# HDMI_CONVERTER.net
KiCad netlist of a schematic drawn in Altium Designer
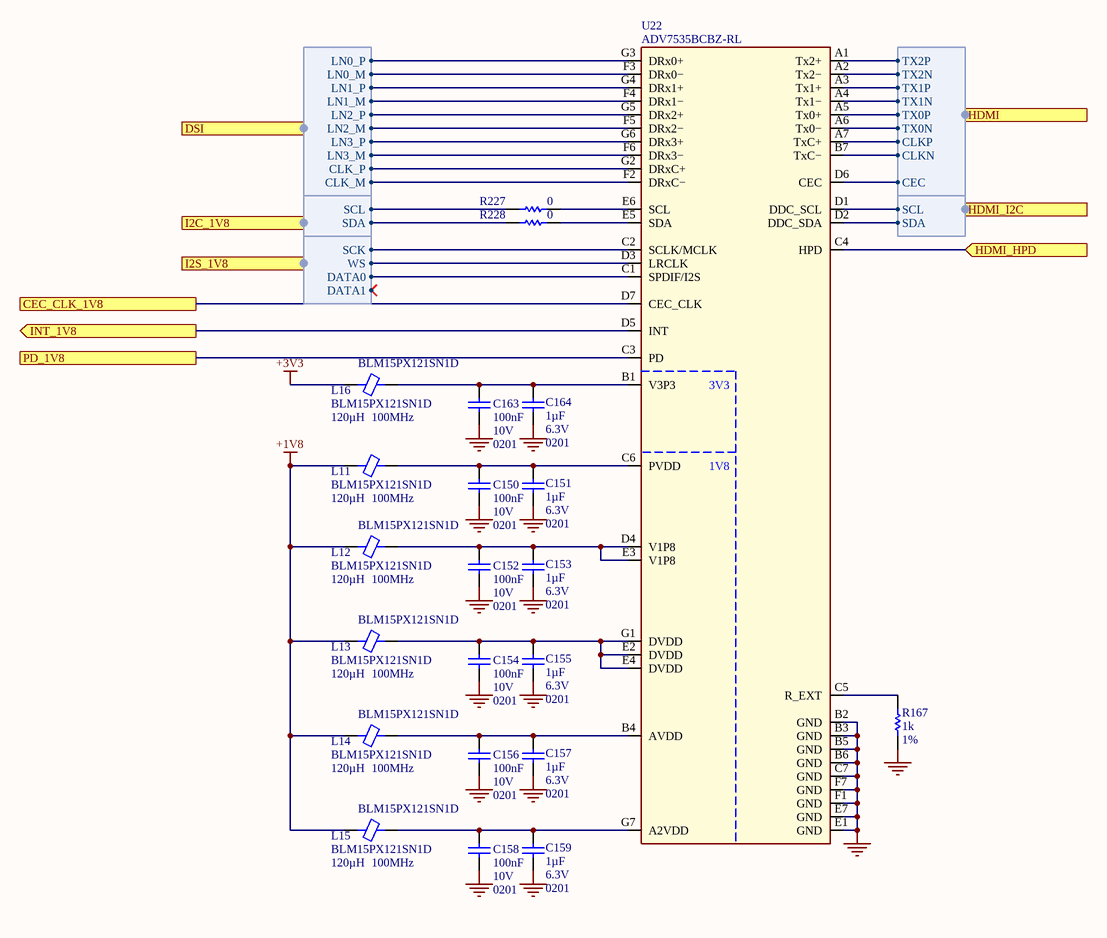
[diagram p0: HDMI_CONVERTER.SchDoc]

(export (version "E")
  (design (tool "Eeschema 10.0.6"))
  (components
    (comp (ref "C150")
      (value "100nF")
      (footprint "CAP-0201")
      (description "CAP CHIP 0201 100nF 10% 10V X5R")
      (fields
        (field (name "PART NUMBER") "CL03A104KP3NNNC")
        (field (name "MANUFACTURER") "Samsung Electro-Mechanics")
        (field (name "VOLTAGE") "10V")
        (field (name "CASE CODE (IMPERIAL)") "0201")
      )
      (libsource (lib "Clean") (part "CAP"))
    )
    (comp (ref "C151")
      (value "1µF")
      (footprint "CAP-0201")
      (description "CAP CHIP 0201 1uF 20% 6.3V X5R")
      (fields
        (field (name "VOLTAGE") "6.3V")
        (field (name "TOLERANCE") "20%")
        (field (name "PART NUMBER") "GRM033R60J105MEA2D")
        (field (name "CASE CODE (IMPERIAL)") "0201")
      )
      (libsource (lib "Clean") (part "CAP"))
    )
    (comp (ref "C152")
      (value "100nF")
      (footprint "CAP-0201")
      (description "CAP CHIP 0201 100nF 10% 10V X5R")
      (fields
        (field (name "PART NUMBER") "CL03A104KP3NNNC")
        (field (name "MANUFACTURER") "Samsung Electro-Mechanics")
        (field (name "VOLTAGE") "10V")
        (field (name "CASE CODE (IMPERIAL)") "0201")
      )
      (libsource (lib "Clean") (part "CAP"))
    )
    (comp (ref "C153")
      (value "1µF")
      (footprint "CAP-0201")
      (description "CAP CHIP 0201 1uF 20% 6.3V X5R")
      (fields
        (field (name "VOLTAGE") "6.3V")
        (field (name "TOLERANCE") "20%")
        (field (name "PART NUMBER") "GRM033R60J105MEA2D")
        (field (name "CASE CODE (IMPERIAL)") "0201")
      )
      (libsource (lib "Clean") (part "CAP"))
    )
    (comp (ref "C154")
      (value "100nF")
      (footprint "CAP-0201")
      (description "CAP CHIP 0201 100nF 10% 10V X5R")
      (fields
        (field (name "PART NUMBER") "CL03A104KP3NNNC")
        (field (name "MANUFACTURER") "Samsung Electro-Mechanics")
        (field (name "VOLTAGE") "10V")
        (field (name "CASE CODE (IMPERIAL)") "0201")
      )
      (libsource (lib "Clean") (part "CAP"))
    )
    (comp (ref "C155")
      (value "1µF")
      (footprint "CAP-0201")
      (description "CAP CHIP 0201 1uF 20% 6.3V X5R")
      (fields
        (field (name "VOLTAGE") "6.3V")
        (field (name "TOLERANCE") "20%")
        (field (name "PART NUMBER") "GRM033R60J105MEA2D")
        (field (name "CASE CODE (IMPERIAL)") "0201")
      )
      (libsource (lib "Clean") (part "CAP"))
    )
    (comp (ref "C156")
      (value "100nF")
      (footprint "CAP-0201")
      (description "CAP CHIP 0201 100nF 10% 10V X5R")
      (fields
        (field (name "PART NUMBER") "CL03A104KP3NNNC")
        (field (name "MANUFACTURER") "Samsung Electro-Mechanics")
        (field (name "VOLTAGE") "10V")
        (field (name "CASE CODE (IMPERIAL)") "0201")
      )
      (libsource (lib "Clean") (part "CAP"))
    )
    (comp (ref "C157")
      (value "1µF")
      (footprint "CAP-0201")
      (description "CAP CHIP 0201 1uF 20% 6.3V X5R")
      (fields
        (field (name "VOLTAGE") "6.3V")
        (field (name "TOLERANCE") "20%")
        (field (name "PART NUMBER") "GRM033R60J105MEA2D")
        (field (name "CASE CODE (IMPERIAL)") "0201")
      )
      (libsource (lib "Clean") (part "CAP"))
    )
    (comp (ref "C158")
      (value "100nF")
      (footprint "CAP-0201")
      (description "CAP CHIP 0201 100nF 10% 10V X5R")
      (fields
        (field (name "PART NUMBER") "CL03A104KP3NNNC")
        (field (name "MANUFACTURER") "Samsung Electro-Mechanics")
        (field (name "VOLTAGE") "10V")
        (field (name "CASE CODE (IMPERIAL)") "0201")
      )
      (libsource (lib "Clean") (part "CAP"))
    )
    (comp (ref "C159")
      (value "1µF")
      (footprint "CAP-0201")
      (description "CAP CHIP 0201 1uF 20% 6.3V X5R")
      (fields
        (field (name "VOLTAGE") "6.3V")
        (field (name "TOLERANCE") "20%")
        (field (name "PART NUMBER") "GRM033R60J105MEA2D")
        (field (name "CASE CODE (IMPERIAL)") "0201")
      )
      (libsource (lib "Clean") (part "CAP"))
    )
    (comp (ref "C163")
      (value "100nF")
      (footprint "CAP-0201")
      (description "CAP CHIP 0201 100nF 10% 10V X5R")
      (fields
        (field (name "PART NUMBER") "CL03A104KP3NNNC")
        (field (name "MANUFACTURER") "Samsung Electro-Mechanics")
        (field (name "VOLTAGE") "10V")
        (field (name "CASE CODE (IMPERIAL)") "0201")
      )
      (libsource (lib "Clean") (part "CAP"))
    )
    (comp (ref "C164")
      (value "1µF")
      (footprint "CAP-0201")
      (description "CAP CHIP 0201 1uF 20% 6.3V X5R")
      (fields
        (field (name "VOLTAGE") "6.3V")
        (field (name "TOLERANCE") "20%")
        (field (name "PART NUMBER") "GRM033R60J105MEA2D")
        (field (name "CASE CODE (IMPERIAL)") "0201")
      )
      (libsource (lib "Clean") (part "CAP"))
    )
    (comp (ref "L11")
      (value "BLM15PX121SN1D")
      (footprint "L-0402")
      (description "FERRITE SMD 0402 120Ohm 25% 100MHz Ferrite 2A")
      (fields
        (field (name "INDUCTANCE") "120µH")
        (field (name "TEST FREQUENCY") "100MHz")
        (field (name "MANUFACTURER") "Murata")
        (field (name "TOLERANCE") "25%")
      )
      (libsource (lib "Clean") (part "Ferrite"))
    )
    (comp (ref "L12")
      (value "BLM15PX121SN1D")
      (footprint "L-0402")
      (description "FERRITE SMD 0402 120Ohm 25% 100MHz Ferrite 2A")
      (fields
        (field (name "INDUCTANCE") "120µH")
        (field (name "TEST FREQUENCY") "100MHz")
        (field (name "MANUFACTURER") "Murata")
        (field (name "TOLERANCE") "25%")
        (field (name "PART NUMBER") "BLM15PX121SN1D")
      )
      (libsource (lib "Clean") (part "Ferrite"))
    )
    (comp (ref "L13")
      (value "BLM15PX121SN1D")
      (footprint "L-0402")
      (description "FERRITE SMD 0402 120Ohm 25% 100MHz Ferrite 2A")
      (fields
        (field (name "INDUCTANCE") "120µH")
        (field (name "TEST FREQUENCY") "100MHz")
        (field (name "MANUFACTURER") "Murata")
        (field (name "TOLERANCE") "25%")
        (field (name "PART NUMBER") "BLM15PX121SN1D")
      )
      (libsource (lib "Clean") (part "Ferrite"))
    )
    (comp (ref "L14")
      (value "BLM15PX121SN1D")
      (footprint "L-0402")
      (description "FERRITE SMD 0402 120Ohm 25% 100MHz Ferrite 2A")
      (fields
        (field (name "INDUCTANCE") "120µH")
        (field (name "TEST FREQUENCY") "100MHz")
        (field (name "MANUFACTURER") "Murata")
        (field (name "TOLERANCE") "25%")
        (field (name "PART NUMBER") "BLM15PX121SN1D")
      )
      (libsource (lib "Clean") (part "Ferrite"))
    )
    (comp (ref "L15")
      (value "BLM15PX121SN1D")
      (footprint "L-0402")
      (description "FERRITE SMD 0402 120Ohm 25% 100MHz Ferrite 2A")
      (fields
        (field (name "INDUCTANCE") "120µH")
        (field (name "TEST FREQUENCY") "100MHz")
        (field (name "MANUFACTURER") "Murata")
        (field (name "TOLERANCE") "25%")
        (field (name "PART NUMBER") "BLM15PX121SN1D")
      )
      (libsource (lib "Clean") (part "Ferrite"))
    )
    (comp (ref "L16")
      (value "BLM15PX121SN1D")
      (footprint "L-0402")
      (description "FERRITE SMD 0402 120Ohm 25% 100MHz Ferrite 2A")
      (fields
        (field (name "INDUCTANCE") "120µH")
        (field (name "TEST FREQUENCY") "100MHz")
        (field (name "MANUFACTURER") "Murata")
        (field (name "TOLERANCE") "25%")
        (field (name "PART NUMBER") "BLM15PX121SN1D")
      )
      (libsource (lib "Clean") (part "Ferrite"))
    )
    (comp (ref "R167")
      (value "1k")
      (footprint "RES-0201")
      (description "RES CHIP 0201 1k 1% 1/20W")
      (fields
        (field (name "PART NUMBER") "RC0201FR-071KL")
        (field (name "TOLERANCE") "1%")
        (field (name "POWER") "50mW")
      )
      (libsource (lib "Clean") (part "RES"))
    )
    (comp (ref "R227")
      (value "0")
      (footprint "RES-0201")
      (description "RES CHIP 0201 0R")
      (fields (field (name "MANUFACTURER") "Vishay") (field (name "PART NUMBER") "CRCW02010000Z0ED"))
      (libsource (lib "Clean") (part "RES"))
    )
    (comp (ref "R228")
      (value "0")
      (footprint "RES-0201")
      (description "RES CHIP 0201 0R")
      (fields (field (name "MANUFACTURER") "Vishay") (field (name "PART NUMBER") "CRCW02010000Z0ED"))
      (libsource (lib "Clean") (part "RES"))
    )
    (comp (ref "U22")
      (value "ADV7535BCBZ-RL")
      (footprint "Analog Devices CB-49-1 WLCSP49 7x7 pitch 0.5mm 3.5x3.5mm")
      (description "IC DSI to HDMI converter, WLCSP49 3.5x3.5mm")
      (fields (field (name "MANUFACTURER") "Analog Devices"))
      (libsource (lib "Clean") (part "ADV7535BCBZ-RL-Symbol-1"))
    )
  )
  (nets
    (net (code "5") (name "+1V8") (class "Default")
      (node (ref "L11") (pin "1") (pinfunction "1_1") (pintype "passive"))
      (node (ref "L12") (pin "1") (pinfunction "1_1") (pintype "passive"))
      (node (ref "L13") (pin "1") (pinfunction "1_1") (pintype "passive"))
      (node (ref "L14") (pin "1") (pinfunction "1_1") (pintype "passive"))
      (node (ref "L15") (pin "1") (pinfunction "1_1") (pintype "passive"))
    )
    (net (code "6") (name "+3V3") (class "Default")
      (node (ref "L16") (pin "1") (pinfunction "1_1") (pintype "passive"))
    )
    (net (code "7") (name "/CEC_CLK_1V8") (class "Default")
      (node (ref "U22") (pin "D7") (pinfunction "CEC_CLK_D7") (pintype "passive"))
    )
    (net (code "8") (name "/HDMI_HPD") (class "Default")
      (node (ref "U22") (pin "C4") (pinfunction "HPD_C4") (pintype "passive"))
    )
    (net (code "10") (name "/INT_1V8") (class "Default")
      (node (ref "U22") (pin "D5") (pinfunction "INT_D5") (pintype "passive"))
    )
    (net (code "11") (name "/PD_1V8") (class "Default")
      (node (ref "U22") (pin "C3") (pinfunction "PD_C3") (pintype "passive"))
    )
    (net (code "15") (name "GND") (class "Default")
      (node (ref "C150") (pin "1") (pinfunction "1_1") (pintype "passive"))
      (node (ref "C151") (pin "1") (pinfunction "1_1") (pintype "passive"))
      (node (ref "C152") (pin "1") (pinfunction "1_1") (pintype "passive"))
      (node (ref "C153") (pin "1") (pinfunction "1_1") (pintype "passive"))
      (node (ref "C154") (pin "1") (pinfunction "1_1") (pintype "passive"))
      (node (ref "C155") (pin "1") (pinfunction "1_1") (pintype "passive"))
      (node (ref "C156") (pin "1") (pinfunction "1_1") (pintype "passive"))
      (node (ref "C157") (pin "1") (pinfunction "1_1") (pintype "passive"))
      (node (ref "C158") (pin "1") (pinfunction "1_1") (pintype "passive"))
      (node (ref "C159") (pin "1") (pinfunction "1_1") (pintype "passive"))
      (node (ref "C163") (pin "1") (pinfunction "1_1") (pintype "passive"))
      (node (ref "C164") (pin "1") (pinfunction "1_1") (pintype "passive"))
      (node (ref "R167") (pin "1") (pinfunction "1_1") (pintype "passive"))
      (node (ref "U22") (pin "B2") (pinfunction "GND_B2") (pintype "passive"))
      (node (ref "U22") (pin "B3") (pinfunction "GND_B3") (pintype "passive"))
      (node (ref "U22") (pin "B5") (pinfunction "GND_B5") (pintype "passive"))
      (node (ref "U22") (pin "B6") (pinfunction "GND_B6") (pintype "passive"))
      (node (ref "U22") (pin "C7") (pinfunction "GND_C7") (pintype "passive"))
      (node (ref "U22") (pin "E1") (pinfunction "GND_E1") (pintype "passive"))
      (node (ref "U22") (pin "E7") (pinfunction "GND_E7") (pintype "passive"))
      (node (ref "U22") (pin "F1") (pinfunction "GND_F1") (pintype "passive"))
      (node (ref "U22") (pin "F7") (pinfunction "GND_F7") (pintype "passive"))
    )
    (net (code "16") (name "Net-(C152-Pad2)") (class "Default")
      (node (ref "C152") (pin "2") (pinfunction "2_2") (pintype "passive"))
      (node (ref "C153") (pin "2") (pinfunction "2_2") (pintype "passive"))
      (node (ref "L12") (pin "2") (pinfunction "2_2") (pintype "passive"))
      (node (ref "U22") (pin "D4") (pinfunction "V1P8_D4") (pintype "passive"))
      (node (ref "U22") (pin "E3") (pinfunction "V1P8_E3") (pintype "passive"))
    )
    (net (code "17") (name "Net-(C154-Pad2)") (class "Default")
      (node (ref "C154") (pin "2") (pinfunction "2_2") (pintype "passive"))
      (node (ref "C155") (pin "2") (pinfunction "2_2") (pintype "passive"))
      (node (ref "L13") (pin "2") (pinfunction "2_2") (pintype "passive"))
      (node (ref "U22") (pin "E2") (pinfunction "DVDD_E2") (pintype "passive"))
      (node (ref "U22") (pin "E4") (pinfunction "DVDD_E4") (pintype "passive"))
      (node (ref "U22") (pin "G1") (pinfunction "DVDD_G1") (pintype "passive"))
    )
    (net (code "18") (name "Net-(U22-A2VDD)") (class "Default")
      (node (ref "C158") (pin "2") (pinfunction "2_2") (pintype "passive"))
      (node (ref "C159") (pin "2") (pinfunction "2_2") (pintype "passive"))
      (node (ref "L15") (pin "2") (pinfunction "2_2") (pintype "passive"))
      (node (ref "U22") (pin "G7") (pinfunction "A2VDD_G7") (pintype "passive"))
    )
    (net (code "19") (name "Net-(U22-AVDD)") (class "Default")
      (node (ref "C156") (pin "2") (pinfunction "2_2") (pintype "passive"))
      (node (ref "C157") (pin "2") (pinfunction "2_2") (pintype "passive"))
      (node (ref "L14") (pin "2") (pinfunction "2_2") (pintype "passive"))
      (node (ref "U22") (pin "B4") (pinfunction "AVDD_B4") (pintype "passive"))
    )
    (net (code "20") (name "Net-(U22-PVDD)") (class "Default")
      (node (ref "C150") (pin "2") (pinfunction "2_2") (pintype "passive"))
      (node (ref "C151") (pin "2") (pinfunction "2_2") (pintype "passive"))
      (node (ref "L11") (pin "2") (pinfunction "2_2") (pintype "passive"))
      (node (ref "U22") (pin "C6") (pinfunction "PVDD_C6") (pintype "passive"))
    )
    (net (code "21") (name "Net-(U22-R_EXT)") (class "Default")
      (node (ref "R167") (pin "2") (pinfunction "2_2") (pintype "passive"))
      (node (ref "U22") (pin "C5") (pinfunction "R_EXT_C5") (pintype "passive"))
    )
    (net (code "22") (name "Net-(U22-SCL)") (class "Default")
      (node (ref "R227") (pin "1") (pinfunction "1_1") (pintype "passive"))
      (node (ref "U22") (pin "E6") (pinfunction "SCL_E6") (pintype "passive"))
    )
    (net (code "23") (name "Net-(U22-SDA)") (class "Default")
      (node (ref "R228") (pin "1") (pinfunction "1_1") (pintype "passive"))
      (node (ref "U22") (pin "E5") (pinfunction "SDA_E5") (pintype "passive"))
    )
    (net (code "24") (name "Net-(U22-V3P3)") (class "Default")
      (node (ref "C163") (pin "2") (pinfunction "2_2") (pintype "passive"))
      (node (ref "C164") (pin "2") (pinfunction "2_2") (pintype "passive"))
      (node (ref "L16") (pin "2") (pinfunction "2_2") (pintype "passive"))
      (node (ref "U22") (pin "B1") (pinfunction "V3P3_B1") (pintype "passive"))
    )
    (net (code "25") (name "unconnected-(R227-Pad2)") (class "Default")
      (node (ref "R227") (pin "2") (pinfunction "2_2") (pintype "passive"))
    )
    (net (code "26") (name "unconnected-(R228-Pad2)") (class "Default")
      (node (ref "R228") (pin "2") (pinfunction "2_2") (pintype "passive"))
    )
    (net (code "27") (name "unconnected-(U22-CEC-PadD6)") (class "Default")
      (node (ref "U22") (pin "D6") (pinfunction "CEC_D6") (pintype "passive"))
    )
    (net (code "28") (name "unconnected-(U22-DDC_SCL-PadD1)") (class "Default")
      (node (ref "U22") (pin "D1") (pinfunction "DDC_SCL_D1") (pintype "passive"))
    )
    (net (code "29") (name "unconnected-(U22-DDC_SDA-PadD2)") (class "Default")
      (node (ref "U22") (pin "D2") (pinfunction "DDC_SDA_D2") (pintype "passive"))
    )
    (net (code "30") (name "unconnected-(U22-DRx0+-PadG3)") (class "Default")
      (node (ref "U22") (pin "G3") (pinfunction "DRx0+_G3") (pintype "passive"))
    )
    (net (code "31") (name "unconnected-(U22-DRx0−-PadF3)") (class "Default")
      (node (ref "U22") (pin "F3") (pinfunction "DRx0−_F3") (pintype "passive"))
    )
    (net (code "32") (name "unconnected-(U22-DRx1+-PadG4)") (class "Default")
      (node (ref "U22") (pin "G4") (pinfunction "DRx1+_G4") (pintype "passive"))
    )
    (net (code "33") (name "unconnected-(U22-DRx1−-PadF4)") (class "Default")
      (node (ref "U22") (pin "F4") (pinfunction "DRx1−_F4") (pintype "passive"))
    )
    (net (code "34") (name "unconnected-(U22-DRx2+-PadG5)") (class "Default")
      (node (ref "U22") (pin "G5") (pinfunction "DRx2+_G5") (pintype "passive"))
    )
    (net (code "35") (name "unconnected-(U22-DRx2−-PadF5)") (class "Default")
      (node (ref "U22") (pin "F5") (pinfunction "DRx2−_F5") (pintype "passive"))
    )
    (net (code "36") (name "unconnected-(U22-DRx3+-PadG6)") (class "Default")
      (node (ref "U22") (pin "G6") (pinfunction "DRx3+_G6") (pintype "passive"))
    )
    (net (code "37") (name "unconnected-(U22-DRx3−-PadF6)") (class "Default")
      (node (ref "U22") (pin "F6") (pinfunction "DRx3−_F6") (pintype "passive"))
    )
    (net (code "38") (name "unconnected-(U22-DRxC+-PadG2)") (class "Default")
      (node (ref "U22") (pin "G2") (pinfunction "DRxC+_G2") (pintype "passive"))
    )
    (net (code "39") (name "unconnected-(U22-DRxC−-PadF2)") (class "Default")
      (node (ref "U22") (pin "F2") (pinfunction "DRxC−_F2") (pintype "passive"))
    )
    (net (code "40") (name "unconnected-(U22-LRCLK-PadD3)") (class "Default")
      (node (ref "U22") (pin "D3") (pinfunction "LRCLK_D3") (pintype "passive"))
    )
    (net (code "41") (name "unconnected-(U22-SCLK{slash}MCLK-PadC2)") (class "Default")
      (node (ref "U22") (pin "C2") (pinfunction "SCLK/MCLK_C2") (pintype "passive"))
    )
    (net (code "42") (name "unconnected-(U22-SPDIF{slash}I2S-PadC1)") (class "Default")
      (node (ref "U22") (pin "C1") (pinfunction "SPDIF/I2S_C1") (pintype "passive"))
    )
    (net (code "43") (name "unconnected-(U22-Tx0+-PadA5)") (class "Default")
      (node (ref "U22") (pin "A5") (pinfunction "Tx0+_A5") (pintype "passive"))
    )
    (net (code "44") (name "unconnected-(U22-Tx0−-PadA6)") (class "Default")
      (node (ref "U22") (pin "A6") (pinfunction "Tx0−_A6") (pintype "passive"))
    )
    (net (code "45") (name "unconnected-(U22-Tx1+-PadA3)") (class "Default")
      (node (ref "U22") (pin "A3") (pinfunction "Tx1+_A3") (pintype "passive"))
    )
    (net (code "46") (name "unconnected-(U22-Tx1−-PadA4)") (class "Default")
      (node (ref "U22") (pin "A4") (pinfunction "Tx1−_A4") (pintype "passive"))
    )
    (net (code "47") (name "unconnected-(U22-Tx2+-PadA1)") (class "Default")
      (node (ref "U22") (pin "A1") (pinfunction "Tx2+_A1") (pintype "passive"))
    )
    (net (code "48") (name "unconnected-(U22-Tx2−-PadA2)") (class "Default")
      (node (ref "U22") (pin "A2") (pinfunction "Tx2−_A2") (pintype "passive"))
    )
    (net (code "49") (name "unconnected-(U22-TxC+-PadA7)") (class "Default")
      (node (ref "U22") (pin "A7") (pinfunction "TxC+_A7") (pintype "passive"))
    )
    (net (code "50") (name "unconnected-(U22-TxC−-PadB7)") (class "Default")
      (node (ref "U22") (pin "B7") (pinfunction "TxC−_B7") (pintype "passive"))
    )
  )
)
